# T-Board-44-84_Etch_-_v0_1.net
KiCad netlist of a schematic drawn in EAGLE
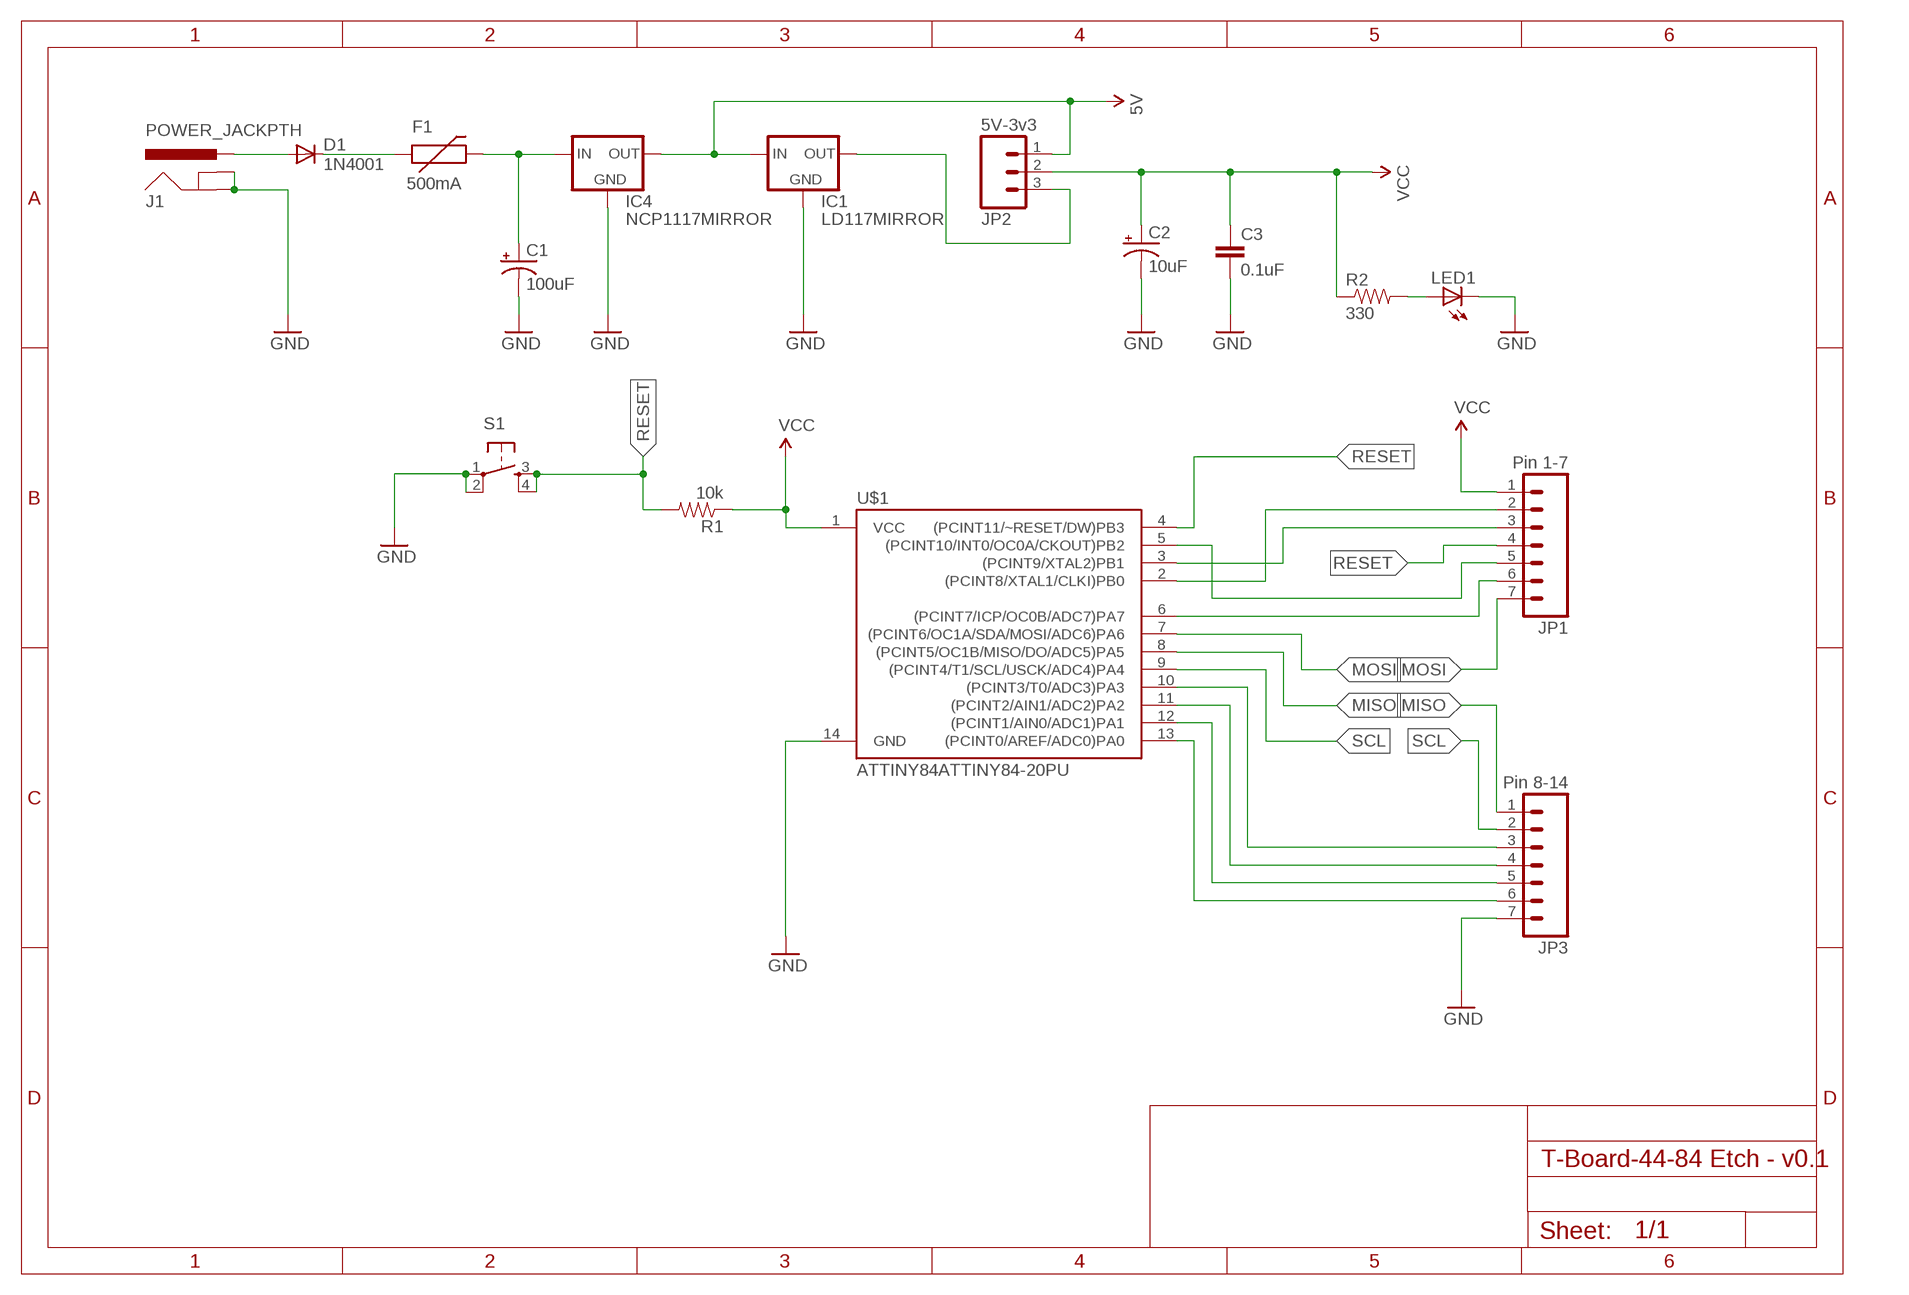
[diagram p0: schematic, sheet 1]

(export (version "E")
  (design (tool "Eeschema 10.0.6"))
  (components
    (comp (ref "C1")
      (value "100uF")
      (footprint "eagle-import:CPOL-RADIAL-100UF-25V")
      (libsource (lib "eagle-import") (part "CAP_POLPTH1"))
    )
    (comp (ref "C2")
      (value "10uF")
      (footprint "eagle-import:CPOL-RADIAL-10UF-25V")
      (libsource (lib "eagle-import") (part "CAP_POLPTH2"))
    )
    (comp (ref "C3")
      (value "0.1uF")
      (footprint "eagle-import:1206")
      (libsource (lib "eagle-import") (part "CAP1206"))
    )
    (comp (ref "D1")
      (value "1N4001")
      (footprint "eagle-import:DIODE-1N4001")
      (libsource (lib "eagle-import") (part "DIODEPTH"))
    )
    (comp (ref "F1")
      (value "500mA")
      (footprint "eagle-import:PTC")
      (libsource (lib "eagle-import") (part "PTCPTH"))
    )
    (comp (ref "IC1")
      (value "LD117MIRROR")
      (footprint "eagle-import:SOT223")
      (libsource (lib "eagle-import") (part "LD117MIRROR"))
    )
    (comp (ref "IC4")
      (value "NCP1117MIRROR")
      (footprint "eagle-import:DPACK")
      (libsource (lib "eagle-import") (part "NCP1117MIRROR"))
    )
    (comp (ref "J1")
      (value "POWER_JACKPTH")
      (footprint "eagle-import:POWER_JACK_PTH")
      (libsource (lib "eagle-import") (part "POWER_JACKPTH"))
    )
    (comp (ref "JP1")
      (value "Pin 1-7")
      (footprint "eagle-import:1X07")
      (libsource (lib "eagle-import") (part "M07"))
    )
    (comp (ref "JP2")
      (value "5V-3v3")
      (footprint "eagle-import:1X03")
      (libsource (lib "eagle-import") (part "M03PTH"))
    )
    (comp (ref "JP3")
      (value "Pin 8-14")
      (footprint "eagle-import:1X07")
      (libsource (lib "eagle-import") (part "M07"))
    )
    (comp (ref "LED1")
      (value "LED1206")
      (footprint "eagle-import:LED-1206")
      (libsource (lib "eagle-import") (part "LED1206"))
    )
    (comp (ref "R1")
      (value "10k")
      (footprint "eagle-import:1206")
      (libsource (lib "eagle-import") (part "RESISTOR1206"))
    )
    (comp (ref "R2")
      (value "330")
      (footprint "eagle-import:1206")
      (libsource (lib "eagle-import") (part "RESISTOR1206"))
    )
    (comp (ref "S1")
      (value "TAC_SWITCHPTH")
      (footprint "eagle-import:TACTILE-PTH")
      (libsource (lib "eagle-import") (part "TAC_SWITCHPTH"))
    )
    (comp (ref "U$1")
      (value "ATTINY84ATTINY84-20PU")
      (footprint "eagle-import:DIL14")
      (libsource (lib "eagle-import") (part "ATTINY84ATTINY84-20PU"))
    )
  )
  (nets
    (net (code "1") (name "5V") (class "Default")
      (node (ref "IC1") (pin "1") (pinfunction "IN_1") (pintype "input"))
      (node (ref "IC4") (pin "4") (pinfunction "OUT_4") (pintype "passive"))
      (node (ref "JP2") (pin "1") (pinfunction "1_1") (pintype "passive"))
    )
    (net (code "2") (name "GND") (class "Default")
      (node (ref "C1") (pin "2") (pinfunction "-_2") (pintype "passive"))
      (node (ref "C2") (pin "2") (pinfunction "-_2") (pintype "passive"))
      (node (ref "C3") (pin "2") (pinfunction "2_2") (pintype "passive"))
      (node (ref "IC1") (pin "3") (pinfunction "GND_3") (pintype "input"))
      (node (ref "IC4") (pin "3") (pinfunction "GND_3") (pintype "input"))
      (node (ref "J1") (pin "GND") (pinfunction "GND_GND") (pintype "bidirectional"))
      (node (ref "J1") (pin "GNDBREAK") (pinfunction "GNDBREAK_GNDBREAK") (pintype "bidirectional"))
      (node (ref "JP3") (pin "7") (pinfunction "7_7") (pintype "passive"))
      (node (ref "LED1") (pin "C") (pinfunction "C_C") (pintype "passive"))
      (node (ref "S1") (pin "1") (pinfunction "1_1") (pintype "passive"))
      (node (ref "S1") (pin "2") (pinfunction "2_2") (pintype "passive"))
      (node (ref "U$1") (pin "14") (pinfunction "GND_14") (pintype "bidirectional"))
    )
    (net (code "3") (name "MISO") (class "Default")
      (node (ref "JP3") (pin "1") (pinfunction "1_1") (pintype "passive"))
      (node (ref "U$1") (pin "8") (pinfunction "(PCINT5/OC1B/MISO/DO/ADC5)PA5_8") (pintype "bidirectional"))
    )
    (net (code "4") (name "MOSI") (class "Default")
      (node (ref "JP1") (pin "7") (pinfunction "7_7") (pintype "passive"))
      (node (ref "U$1") (pin "7") (pinfunction "(PCINT6/OC1A/SDA/MOSI/ADC6)PA6_7") (pintype "bidirectional"))
    )
    (net (code "5") (name "Net-(C1-+)") (class "Default")
      (node (ref "C1") (pin "1") (pinfunction "+_1") (pintype "passive"))
      (node (ref "F1") (pin "P$2") (pinfunction "2_P$2") (pintype "bidirectional"))
      (node (ref "IC4") (pin "1") (pinfunction "IN_1") (pintype "input"))
    )
    (net (code "6") (name "Net-(D1-PadA)") (class "Default")
      (node (ref "D1") (pin "A") (pinfunction "A_A") (pintype "passive"))
      (node (ref "J1") (pin "PWR") (pinfunction "PWR_PWR") (pintype "bidirectional"))
    )
    (net (code "7") (name "Net-(F1-1)") (class "Default")
      (node (ref "D1") (pin "C") (pinfunction "C_C") (pintype "passive"))
      (node (ref "F1") (pin "P$1") (pinfunction "1_P$1") (pintype "bidirectional"))
    )
    (net (code "8") (name "Net-(IC1-OUT)") (class "Default")
      (node (ref "IC1") (pin "4") (pinfunction "OUT_4") (pintype "passive"))
      (node (ref "JP2") (pin "3") (pinfunction "3_3") (pintype "passive"))
    )
    (net (code "9") (name "Net-(LED1-PadA)") (class "Default")
      (node (ref "LED1") (pin "A") (pinfunction "A_A") (pintype "passive"))
      (node (ref "R2") (pin "2") (pinfunction "2_2") (pintype "passive"))
    )
    (net (code "10") (name "Net-(U$1-(PCINT0{slash}AREF{slash}ADC0)PA0)") (class "Default")
      (node (ref "JP3") (pin "6") (pinfunction "6_6") (pintype "passive"))
      (node (ref "U$1") (pin "13") (pinfunction "(PCINT0/AREF/ADC0)PA0_13") (pintype "bidirectional"))
    )
    (net (code "11") (name "Net-(U$1-(PCINT1{slash}AIN0{slash}ADC1)PA1)") (class "Default")
      (node (ref "JP3") (pin "5") (pinfunction "5_5") (pintype "passive"))
      (node (ref "U$1") (pin "12") (pinfunction "(PCINT1/AIN0/ADC1)PA1_12") (pintype "bidirectional"))
    )
    (net (code "12") (name "Net-(U$1-(PCINT2{slash}AIN1{slash}ADC2)PA2)") (class "Default")
      (node (ref "JP3") (pin "4") (pinfunction "4_4") (pintype "passive"))
      (node (ref "U$1") (pin "11") (pinfunction "(PCINT2/AIN1/ADC2)PA2_11") (pintype "bidirectional"))
    )
    (net (code "13") (name "Net-(U$1-(PCINT3{slash}T0{slash}ADC3)PA3)") (class "Default")
      (node (ref "JP3") (pin "3") (pinfunction "3_3") (pintype "passive"))
      (node (ref "U$1") (pin "10") (pinfunction "(PCINT3/T0/ADC3)PA3_10") (pintype "bidirectional"))
    )
    (net (code "14") (name "Net-(U$1-(PCINT7{slash}ICP{slash}OC0B{slash}ADC7)PA7)") (class "Default")
      (node (ref "JP1") (pin "6") (pinfunction "6_6") (pintype "passive"))
      (node (ref "U$1") (pin "6") (pinfunction "(PCINT7/ICP/OC0B/ADC7)PA7_6") (pintype "bidirectional"))
    )
    (net (code "15") (name "Net-(U$1-(PCINT8{slash}XTAL1{slash}CLKI)PB0)") (class "Default")
      (node (ref "JP1") (pin "2") (pinfunction "2_2") (pintype "passive"))
      (node (ref "U$1") (pin "2") (pinfunction "(PCINT8/XTAL1/CLKI)PB0_2") (pintype "bidirectional"))
    )
    (net (code "16") (name "Net-(U$1-(PCINT9{slash}XTAL2)PB1)") (class "Default")
      (node (ref "JP1") (pin "3") (pinfunction "3_3") (pintype "passive"))
      (node (ref "U$1") (pin "3") (pinfunction "(PCINT9/XTAL2)PB1_3") (pintype "bidirectional"))
    )
    (net (code "17") (name "Net-(U$1-(PCINT10{slash}INT0{slash}OC0A{slash}CKOUT)PB2)") (class "Default")
      (node (ref "JP1") (pin "5") (pinfunction "5_5") (pintype "passive"))
      (node (ref "U$1") (pin "5") (pinfunction "(PCINT10/INT0/OC0A/CKOUT)PB2_5") (pintype "bidirectional"))
    )
    (net (code "18") (name "RESET") (class "Default")
      (node (ref "JP1") (pin "4") (pinfunction "4_4") (pintype "passive"))
      (node (ref "R1") (pin "2") (pinfunction "2_2") (pintype "passive"))
      (node (ref "S1") (pin "3") (pinfunction "3_3") (pintype "passive"))
      (node (ref "S1") (pin "4") (pinfunction "4_4") (pintype "passive"))
      (node (ref "U$1") (pin "4") (pinfunction "(PCINT11/~{RESET/DW})PB3_4") (pintype "bidirectional"))
    )
    (net (code "19") (name "SCL") (class "Default")
      (node (ref "JP3") (pin "2") (pinfunction "2_2") (pintype "passive"))
      (node (ref "U$1") (pin "9") (pinfunction "(PCINT4/T1/SCL/USCK/ADC4)PA4_9") (pintype "bidirectional"))
    )
    (net (code "20") (name "VCC") (class "Default")
      (node (ref "C2") (pin "1") (pinfunction "+_1") (pintype "passive"))
      (node (ref "C3") (pin "1") (pinfunction "1_1") (pintype "passive"))
      (node (ref "JP1") (pin "1") (pinfunction "1_1") (pintype "passive"))
      (node (ref "JP2") (pin "2") (pinfunction "2_2") (pintype "passive"))
      (node (ref "R1") (pin "1") (pinfunction "1_1") (pintype "passive"))
      (node (ref "R2") (pin "1") (pinfunction "1_1") (pintype "passive"))
      (node (ref "U$1") (pin "1") (pinfunction "VCC_1") (pintype "bidirectional"))
    )
  )
)
